# SH8_-_CAN.net
KiCad netlist of a schematic drawn in Altium Designer
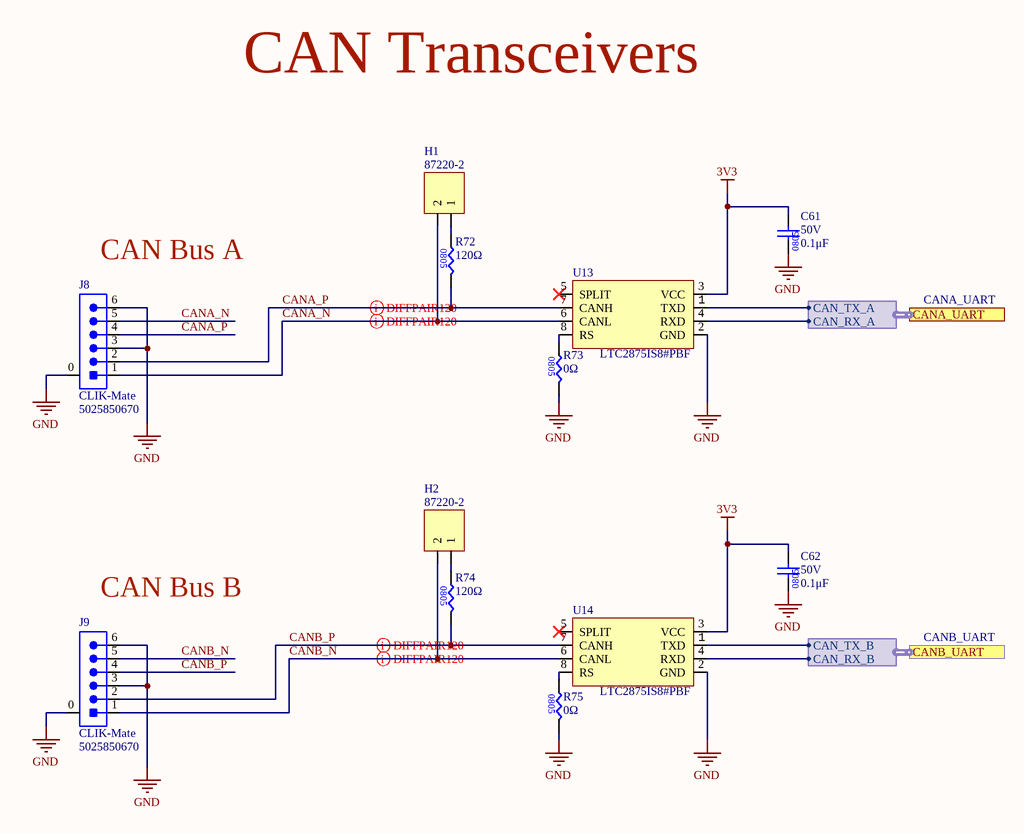
[diagram p0: SH8 - CAN.SchDoc]

(export (version "E")
  (design (tool "Eeschema 10.0.6"))
  (components
    (comp (ref "C61")
      (value "0.1μF")
      (footprint "CAP2012")
      (description "CAP CER 0.1UF 50V X7R 0805")
      (fields
        (field (name "VOLTAGE RATING") "50V")
        (field (name "LCSC PART #") "C49678")
        (field (name "Comment") "CAP_0.1uF_50V_0805")
      )
      (libsource (lib "UWRT_Schematic_Library_2020") (part "CAP_0.1uF_50V_0805"))
    )
    (comp (ref "C62")
      (value "0.1μF")
      (footprint "CAP2012")
      (description "CAP CER 0.1UF 50V X7R 0805")
      (fields
        (field (name "VOLTAGE RATING") "50V")
        (field (name "LCSC PART #") "C49678")
        (field (name "Comment") "CAP_0.1uF_50V_0805")
      )
      (libsource (lib "UWRT_Schematic_Library_2020") (part "CAP_0.1uF_50V_0805"))
    )
    (comp (ref "H1")
      (value "JUMPER_2")
      (footprint "HDR1X2")
      (description "HEADER 2X1")
      (fields (field (name "MANUFACTURER PART NUMBER 1") "87220-2"))
      (libsource (lib "UWRT_Schematic_Library_2020") (part "JUMPER_2"))
    )
    (comp (ref "H2")
      (value "JUMPER_2")
      (footprint "HDR1X2")
      (description "HEADER 2X1")
      (fields (field (name "MANUFACTURER PART NUMBER 1") "87220-2"))
      (libsource (lib "UWRT_Schematic_Library_2020") (part "JUMPER_2"))
    )
    (comp (ref "J8")
      (value "CON_6M_SM_RA_1.5mm")
      (footprint "MOLEX-5025850670")
      (description "CONN HEADER SMD RIGHT ANGLE 1.5 MM PITCH")
      (fields (field (name "FAMILY") "CLIK-Mate") (field (name "MANUFACTURER PART NUMBER 1") "5025850670"))
      (libsource (lib "UWRT_Schematic_Library_2020") (part "CON_6M_SM_RA_1.5mm"))
    )
    (comp (ref "J9")
      (value "CON_6M_SM_RA_1.5mm")
      (footprint "MOLEX-5025850670")
      (description "CONN HEADER SMD RIGHT ANGLE 1.5 MM PITCH")
      (fields (field (name "FAMILY") "CLIK-Mate") (field (name "MANUFACTURER PART NUMBER 1") "5025850670"))
      (libsource (lib "UWRT_Schematic_Library_2020") (part "CON_6M_SM_RA_1.5mm"))
    )
    (comp (ref "R72")
      (value "120Ω")
      (footprint "RES0805")
      (description "RES 120 OHM 1% 1/8W 0805")
      (fields (field (name "LCSC PART #") "C17437") (field (name "Comment") "RES_120Ω_0805_1%"))
      (libsource (lib "UWRT_Schematic_Library_2020") (part "RES_120Ω_0805_1%"))
    )
    (comp (ref "R73")
      (value "0Ω")
      (footprint "RES0805")
      (description "RES 0 OHM JUMPER 1/8W 0805")
      (fields (field (name "LCSC PART #") "C17477") (field (name "Comment") "RES_0Ω_0805"))
      (libsource (lib "UWRT_Schematic_Library_2020") (part "RES_0Ω_0805"))
    )
    (comp (ref "R74")
      (value "120Ω")
      (footprint "RES0805")
      (description "RES 120 OHM 1% 1/8W 0805")
      (fields (field (name "LCSC PART #") "C17437") (field (name "Comment") "RES_120Ω_0805_1%"))
      (libsource (lib "UWRT_Schematic_Library_2020") (part "RES_120Ω_0805_1%"))
    )
    (comp (ref "R75")
      (value "0Ω")
      (footprint "RES0805")
      (description "RES 0 OHM JUMPER 1/8W 0805")
      (fields (field (name "LCSC PART #") "C17477") (field (name "Comment") "RES_0Ω_0805"))
      (libsource (lib "UWRT_Schematic_Library_2020") (part "RES_0Ω_0805"))
    )
    (comp (ref "U13")
      (value "LTC2875")
      (footprint "LT-S8_N")
      (description "IC TXRX CAN 4MBPS 8SO")
      (fields
        (field (name "MANUFACTURER PART NUMBER 1") "LTC2875IS8#PBF")
        (field (name "LCSC PART #") "C117076")
      )
      (libsource (lib "UWRT_Schematic_Library_2020") (part "LTC2875"))
    )
    (comp (ref "U14")
      (value "LTC2875")
      (footprint "LT-S8_N")
      (description "IC TXRX CAN 4MBPS 8SO")
      (fields
        (field (name "MANUFACTURER PART NUMBER 1") "LTC2875IS8#PBF")
        (field (name "LCSC PART #") "C117076")
      )
      (libsource (lib "UWRT_Schematic_Library_2020") (part "LTC2875"))
    )
  )
  (nets
    (net (code "3") (name "/CANA_N") (class "Default")
      (node (ref "H1") (pin "2") (pinfunction "2_2") (pintype "passive"))
      (node (ref "J8") (pin "1") (pinfunction "1_1") (pintype "passive"))
      (node (ref "J8") (pin "5") (pinfunction "5_5") (pintype "passive"))
      (node (ref "U13") (pin "6") (pinfunction "CANL_6") (pintype "passive"))
    )
    (net (code "4") (name "/CANA_P") (class "Default")
      (node (ref "J8") (pin "2") (pinfunction "2_2") (pintype "passive"))
      (node (ref "J8") (pin "4") (pinfunction "4_4") (pintype "passive"))
      (node (ref "R72") (pin "2") (pinfunction "2_2") (pintype "passive"))
      (node (ref "U13") (pin "7") (pinfunction "CANH_7") (pintype "passive"))
    )
    (net (code "5") (name "/CANB_N") (class "Default")
      (node (ref "H2") (pin "2") (pinfunction "2_2") (pintype "passive"))
      (node (ref "J9") (pin "1") (pinfunction "1_1") (pintype "passive"))
      (node (ref "J9") (pin "5") (pinfunction "5_5") (pintype "passive"))
      (node (ref "U14") (pin "6") (pinfunction "CANL_6") (pintype "passive"))
    )
    (net (code "6") (name "/CANB_P") (class "Default")
      (node (ref "J9") (pin "2") (pinfunction "2_2") (pintype "passive"))
      (node (ref "J9") (pin "4") (pinfunction "4_4") (pintype "passive"))
      (node (ref "R74") (pin "2") (pinfunction "2_2") (pintype "passive"))
      (node (ref "U14") (pin "7") (pinfunction "CANH_7") (pintype "passive"))
    )
    (net (code "7") (name "/CAN_RX_A") (class "Default")
      (node (ref "U13") (pin "4") (pinfunction "RXD_4") (pintype "passive"))
    )
    (net (code "8") (name "/CAN_RX_B") (class "Default")
      (node (ref "U14") (pin "4") (pinfunction "RXD_4") (pintype "passive"))
    )
    (net (code "9") (name "/CAN_TX_A") (class "Default")
      (node (ref "U13") (pin "1") (pinfunction "TXD_1") (pintype "passive"))
    )
    (net (code "10") (name "/CAN_TX_B") (class "Default")
      (node (ref "U14") (pin "1") (pinfunction "TXD_1") (pintype "passive"))
    )
    (net (code "13") (name "3V3") (class "Default")
      (node (ref "C61") (pin "2") (pinfunction "2_2") (pintype "passive"))
      (node (ref "C62") (pin "2") (pinfunction "2_2") (pintype "passive"))
      (node (ref "U13") (pin "3") (pinfunction "VCC_3") (pintype "passive"))
      (node (ref "U14") (pin "3") (pinfunction "VCC_3") (pintype "passive"))
    )
    (net (code "14") (name "GND") (class "Default")
      (node (ref "C61") (pin "1") (pinfunction "1_1") (pintype "passive"))
      (node (ref "C62") (pin "1") (pinfunction "1_1") (pintype "passive"))
      (node (ref "J8") (pin "0") (pinfunction "0_0") (pintype "passive"))
      (node (ref "J8") (pin "3") (pinfunction "3_3") (pintype "passive"))
      (node (ref "J8") (pin "6") (pinfunction "6_6") (pintype "passive"))
      (node (ref "J9") (pin "0") (pinfunction "0_0") (pintype "passive"))
      (node (ref "J9") (pin "3") (pinfunction "3_3") (pintype "passive"))
      (node (ref "J9") (pin "6") (pinfunction "6_6") (pintype "passive"))
      (node (ref "R73") (pin "2") (pinfunction "2_2") (pintype "passive"))
      (node (ref "R75") (pin "2") (pinfunction "2_2") (pintype "passive"))
      (node (ref "U13") (pin "2") (pinfunction "GND_2") (pintype "passive"))
      (node (ref "U14") (pin "2") (pinfunction "GND_2") (pintype "passive"))
    )
    (net (code "15") (name "Net-(H1-Pad1)") (class "Default")
      (node (ref "H1") (pin "1") (pinfunction "1_1") (pintype "passive"))
      (node (ref "R72") (pin "1") (pinfunction "1_1") (pintype "passive"))
    )
    (net (code "16") (name "Net-(H2-Pad1)") (class "Default")
      (node (ref "H2") (pin "1") (pinfunction "1_1") (pintype "passive"))
      (node (ref "R74") (pin "1") (pinfunction "1_1") (pintype "passive"))
    )
    (net (code "17") (name "Net-(U13-RS)") (class "Default")
      (node (ref "R73") (pin "1") (pinfunction "1_1") (pintype "passive"))
      (node (ref "U13") (pin "8") (pinfunction "RS_8") (pintype "passive"))
    )
    (net (code "18") (name "Net-(U14-RS)") (class "Default")
      (node (ref "R75") (pin "1") (pinfunction "1_1") (pintype "passive"))
      (node (ref "U14") (pin "8") (pinfunction "RS_8") (pintype "passive"))
    )
    (net (code "19") (name "unconnected-(U13-SPLIT-Pad5)") (class "Default")
      (node (ref "U13") (pin "5") (pinfunction "SPLIT_5") (pintype "passive+no_connect"))
    )
    (net (code "20") (name "unconnected-(U14-SPLIT-Pad5)") (class "Default")
      (node (ref "U14") (pin "5") (pinfunction "SPLIT_5") (pintype "passive+no_connect"))
    )
  )
)
